# BreakoutBoard.net
KiCad netlist of a schematic drawn in Altium Designer
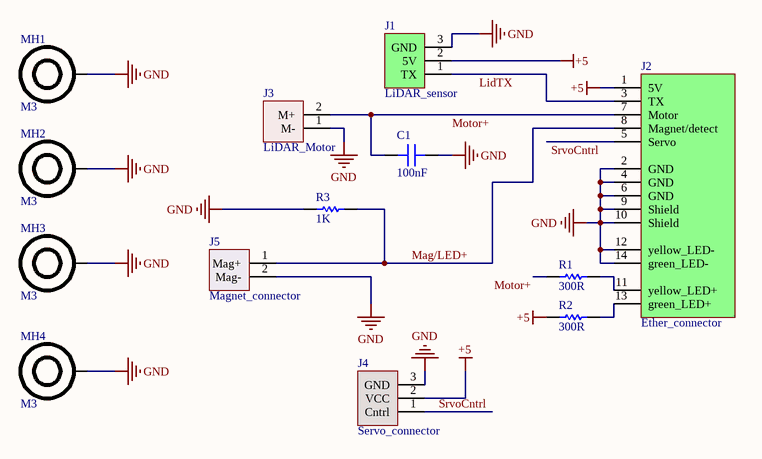
[diagram p0: BreakoutBoard.SchDoc]

(export (version "E")
  (design (tool "Eeschema 10.0.6"))
  (components
    (comp (ref "C1")
      (value "100nF")
      (footprint "CAP 0603")
      (description "SMT Capacitor")
      (libsource (lib "Breakout") (part "Capacitor"))
    )
    (comp (ref "J1")
      (value "LiDAR_sensor")
      (footprint "JST XH B3B-XH-A")
      (libsource (lib "Breakout") (part "LiDAR_sensor"))
    )
    (comp (ref "J2")
      (value "Ether_connector")
      (footprint "MTJ88ARX1FSMLG")
      (libsource (lib "Breakout") (part "Ether_connector"))
    )
    (comp (ref "J3")
      (value "LiDAR_Motor")
      (footprint "JST XH B2B-XH-A")
      (libsource (lib "Breakout") (part "LiDAR_Motor"))
    )
    (comp (ref "J4")
      (value "Servo_connector")
      (footprint "JST XH B3B-XH-A")
      (libsource (lib "Breakout") (part "Servo_connector"))
    )
    (comp (ref "J5")
      (value "Magnet_connector")
      (footprint "JST XH B2B-XH-A")
      (libsource (lib "Breakout") (part "Magnet_connector"))
    )
    (comp (ref "MH1") (value "M3") (footprint "SCREW_M3.0") (libsource (lib "Breakout") (part "SCREW")))
    (comp (ref "MH2") (value "M3") (footprint "SCREW_M3.0") (libsource (lib "Breakout") (part "SCREW")))
    (comp (ref "MH3") (value "M3") (footprint "SCREW_M3.0") (libsource (lib "Breakout") (part "SCREW")))
    (comp (ref "MH4") (value "M3") (footprint "SCREW_M3.0") (libsource (lib "Breakout") (part "SCREW")))
    (comp (ref "R1")
      (value "300R")
      (footprint "RES 0603")
      (description "Resistor")
      (fields (field (name "PUBLISHER") "Altium Limited"))
      (libsource (lib "Breakout") (part "Res"))
    )
    (comp (ref "R2")
      (value "300R")
      (footprint "RES 0603")
      (description "Resistor")
      (fields (field (name "PUBLISHER") "Altium Limited"))
      (libsource (lib "Breakout") (part "Res"))
    )
    (comp (ref "R3")
      (value "1K")
      (footprint "RES 0603")
      (description "Resistor")
      (fields (field (name "PUBLISHER") "Altium Limited"))
      (libsource (lib "Breakout") (part "Res"))
    )
  )
  (nets
    (net (code "1") (name "+5") (class "Default")
      (node (ref "J1") (pin "2") (pinfunction "5V_2") (pintype "passive"))
      (node (ref "J2") (pin "1") (pinfunction "5V_1") (pintype "passive"))
      (node (ref "J4") (pin "2") (pinfunction "VCC_2") (pintype "passive"))
      (node (ref "R2") (pin "1") (pinfunction "1_1") (pintype "passive"))
    )
    (net (code "2") (name "/LidTX") (class "Default")
      (node (ref "J1") (pin "1") (pinfunction "TX_1") (pintype "passive"))
      (node (ref "J2") (pin "3") (pinfunction "TX_3") (pintype "passive"))
    )
    (net (code "3") (name "/Mag{slash}LED+") (class "Default")
      (node (ref "J2") (pin "8") (pinfunction "Magnet/detect_8") (pintype "passive"))
      (node (ref "J5") (pin "1") (pinfunction "Mag+_1") (pintype "passive"))
      (node (ref "R3") (pin "2") (pinfunction "2_2") (pintype "passive"))
    )
    (net (code "4") (name "/Motor+") (class "Default")
      (node (ref "C1") (pin "1") (pinfunction "1_1") (pintype "passive"))
      (node (ref "J2") (pin "7") (pinfunction "Motor_7") (pintype "passive"))
      (node (ref "J3") (pin "2") (pinfunction "M+_2") (pintype "passive"))
      (node (ref "R1") (pin "1") (pinfunction "1_1") (pintype "passive"))
    )
    (net (code "5") (name "/SrvoCntrl") (class "Default")
      (node (ref "J2") (pin "5") (pinfunction "Servo_5") (pintype "passive"))
      (node (ref "J4") (pin "1") (pinfunction "Cntrl_1") (pintype "passive"))
    )
    (net (code "6") (name "GND") (class "Default")
      (node (ref "C1") (pin "2") (pinfunction "2_2") (pintype "passive"))
      (node (ref "J1") (pin "3") (pinfunction "GND_3") (pintype "passive"))
      (node (ref "J2") (pin "10") (pinfunction "Shield_10") (pintype "passive"))
      (node (ref "J2") (pin "12") (pinfunction "yellow_LED-_12") (pintype "passive"))
      (node (ref "J2") (pin "14") (pinfunction "green_LED-_14") (pintype "passive"))
      (node (ref "J2") (pin "2") (pinfunction "GND_2") (pintype "passive"))
      (node (ref "J2") (pin "4") (pinfunction "GND_4") (pintype "passive"))
      (node (ref "J2") (pin "6") (pinfunction "GND_6") (pintype "passive"))
      (node (ref "J2") (pin "9") (pinfunction "Shield_9") (pintype "passive"))
      (node (ref "J3") (pin "1") (pinfunction "M-_1") (pintype "passive"))
      (node (ref "J4") (pin "3") (pinfunction "GND_3") (pintype "passive"))
      (node (ref "J5") (pin "2") (pinfunction "Mag-_2") (pintype "passive"))
      (node (ref "MH1") (pin "1") (pinfunction "1_1") (pintype "passive"))
      (node (ref "MH2") (pin "1") (pinfunction "1_1") (pintype "passive"))
      (node (ref "MH3") (pin "1") (pinfunction "1_1") (pintype "passive"))
      (node (ref "MH4") (pin "1") (pinfunction "1_1") (pintype "passive"))
      (node (ref "R3") (pin "1") (pinfunction "1_1") (pintype "passive"))
    )
    (net (code "7") (name "Net-(J2-green_LED+)") (class "Default")
      (node (ref "J2") (pin "13") (pinfunction "green_LED+_13") (pintype "passive"))
      (node (ref "R2") (pin "2") (pinfunction "2_2") (pintype "passive"))
    )
    (net (code "8") (name "Net-(J2-yellow_LED+)") (class "Default")
      (node (ref "J2") (pin "11") (pinfunction "yellow_LED+_11") (pintype "passive"))
      (node (ref "R1") (pin "2") (pinfunction "2_2") (pintype "passive"))
    )
  )
)
